# Control.net
KiCad netlist of a schematic drawn in Altium Designer
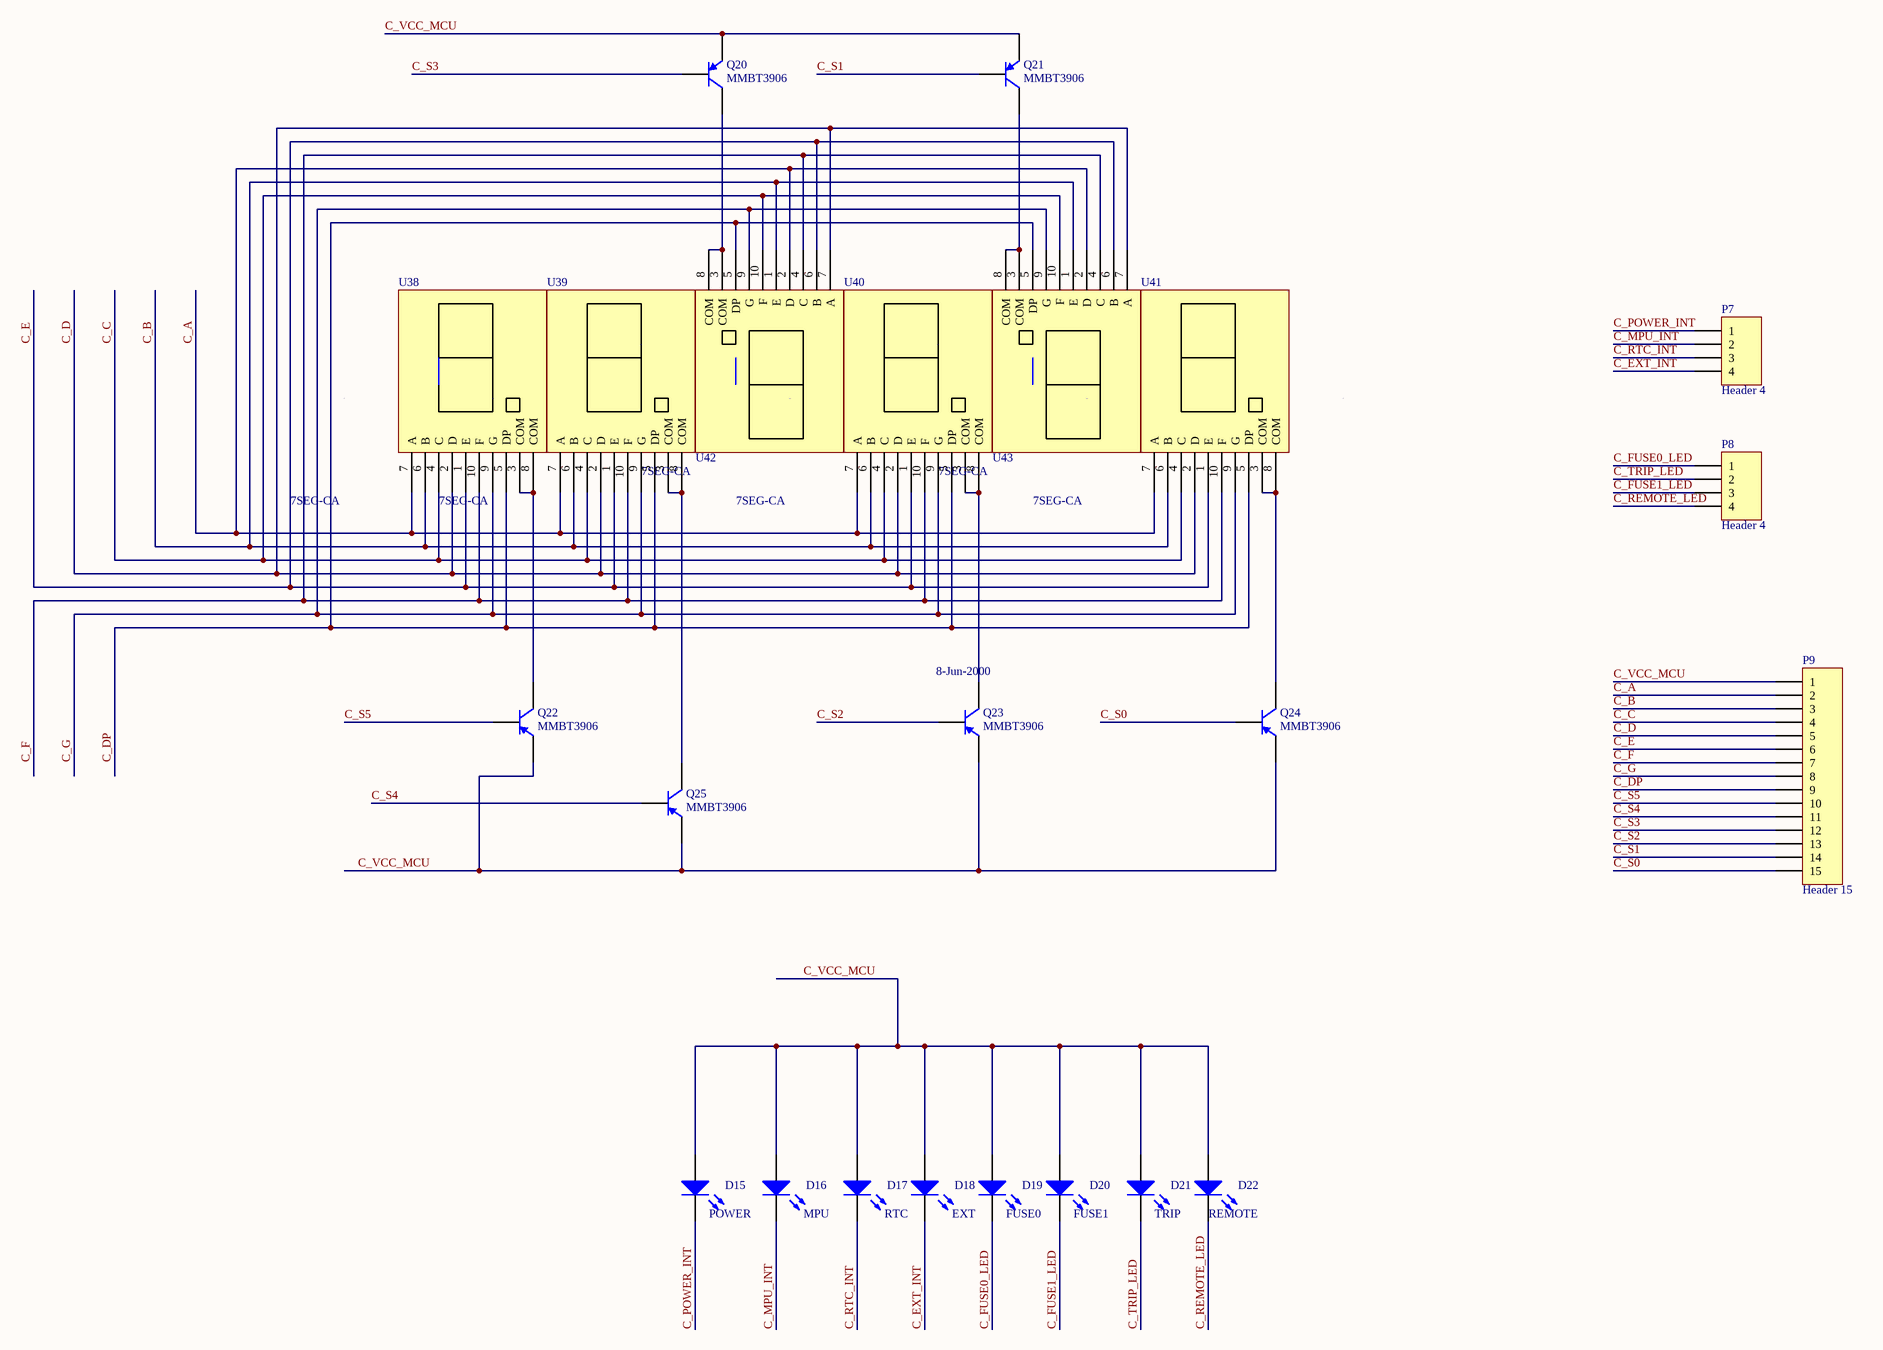
[diagram p0: Control.SchDoc]

(export (version "E")
  (design (tool "Eeschema 10.0.6"))
  (components
    (comp (ref "D15")
      (value "LED")
      (footprint "clock:0603D")
      (description "Typical RED, GREEN, YELLOW, AMBER GaAs LED")
      (fields (field (name "INFOR") "POWER") (field (name "PUBLISHER") "Altium Limited"))
      (libsource (lib "Miscellaneous Devices") (part "LED2"))
    )
    (comp (ref "D16")
      (value "LED")
      (footprint "clock:0603D")
      (description "Typical RED, GREEN, YELLOW, AMBER GaAs LED")
      (fields (field (name "INFO") "MPU") (field (name "PUBLISHER") "Altium Limited"))
      (libsource (lib "Miscellaneous Devices") (part "LED2"))
    )
    (comp (ref "D17")
      (value "LED")
      (footprint "clock:0603D")
      (description "Typical RED, GREEN, YELLOW, AMBER GaAs LED")
      (fields (field (name "INFO") "RTC") (field (name "PUBLISHER") "Altium Limited"))
      (libsource (lib "Miscellaneous Devices") (part "LED2"))
    )
    (comp (ref "D18")
      (value "LED")
      (footprint "clock:0603D")
      (description "Typical RED, GREEN, YELLOW, AMBER GaAs LED")
      (fields (field (name "INFO") "EXT") (field (name "PUBLISHER") "Altium Limited"))
      (libsource (lib "Miscellaneous Devices") (part "LED2"))
    )
    (comp (ref "D19")
      (value "LED")
      (footprint "clock:0603D")
      (description "Typical RED, GREEN, YELLOW, AMBER GaAs LED")
      (fields (field (name "INFO") "FUSE0") (field (name "PUBLISHER") "Altium Limited"))
      (libsource (lib "Miscellaneous Devices") (part "LED2"))
    )
    (comp (ref "D20")
      (value "LED")
      (footprint "clock:0603D")
      (description "Typical RED, GREEN, YELLOW, AMBER GaAs LED")
      (fields (field (name "INFO") "FUSE1") (field (name "PUBLISHER") "Altium Limited"))
      (libsource (lib "Miscellaneous Devices") (part "LED2"))
    )
    (comp (ref "D21")
      (value "LED")
      (footprint "clock:0603D")
      (description "Typical RED, GREEN, YELLOW, AMBER GaAs LED")
      (fields (field (name "INFO") "TRIP") (field (name "PUBLISHER") "Altium Limited"))
      (libsource (lib "Miscellaneous Devices") (part "LED2"))
    )
    (comp (ref "D22")
      (value "LED")
      (footprint "clock:0603D")
      (description "Typical RED, GREEN, YELLOW, AMBER GaAs LED")
      (fields (field (name "INFO") "REMOTE") (field (name "PUBLISHER") "Altium Limited"))
      (libsource (lib "Miscellaneous Devices") (part "LED2"))
    )
    (comp (ref "P7")
      (value "Header 4")
      (footprint "HDR1X4")
      (description "Header, 4-Pin")
      (fields (field (name "PUBLISHER") "Altium Limited"))
      (libsource (lib "Miscellaneous Connectors") (part "Header 4"))
    )
    (comp (ref "P8")
      (value "Header 4")
      (footprint "HDR1X4")
      (description "Header, 4-Pin")
      (fields (field (name "PUBLISHER") "Altium Limited"))
      (libsource (lib "Miscellaneous Connectors") (part "Header 4"))
    )
    (comp (ref "P9")
      (value "Header 15")
      (footprint "clock:HDR1X15")
      (description "Header, 15-Pin")
      (fields (field (name "PUBLISHER") "Altium Limited"))
      (libsource (lib "Miscellaneous Connectors") (part "Header 15"))
    )
    (comp (ref "Q20")
      (value "MMBT3906")
      (footprint "clock:SOT23-3-PNP")
      (description "PNP Bipolar Transistor")
      (fields (field (name "PUBLISHER") "Altium Limited"))
      (libsource (lib "Miscellaneous Devices") (part "PNP"))
    )
    (comp (ref "Q21")
      (value "MMBT3906")
      (footprint "clock:SOT23-3-PNP")
      (description "PNP Bipolar Transistor")
      (fields (field (name "PUBLISHER") "Altium Limited"))
      (libsource (lib "Miscellaneous Devices") (part "PNP"))
    )
    (comp (ref "Q22")
      (value "MMBT3906")
      (footprint "clock:SOT23-3-PNP")
      (description "PNP Bipolar Transistor")
      (fields (field (name "PUBLISHER") "Altium Limited"))
      (libsource (lib "Miscellaneous Devices") (part "PNP"))
    )
    (comp (ref "Q23")
      (value "MMBT3906")
      (footprint "clock:SOT23-3-PNP")
      (description "PNP Bipolar Transistor")
      (fields (field (name "PUBLISHED") "8-Jun-2000") (field (name "PUBLISHER") "Altium Limited"))
      (libsource (lib "Miscellaneous Devices") (part "PNP"))
    )
    (comp (ref "Q24")
      (value "MMBT3906")
      (footprint "clock:SOT23-3-PNP")
      (description "PNP Bipolar Transistor")
      (fields (field (name "PUBLISHER") "Altium Limited"))
      (libsource (lib "Miscellaneous Devices") (part "PNP"))
    )
    (comp (ref "Q25")
      (value "MMBT3906")
      (footprint "clock:SOT23-3-PNP")
      (description "PNP Bipolar Transistor")
      (fields (field (name "PUBLISHER") "Altium Limited"))
      (libsource (lib "Miscellaneous Devices") (part "PNP"))
    )
    (comp (ref "U38")
      (value "7SEG-CA")
      (footprint "clock:8SEC-CA-28")
      (libsource (lib "") (part "7SEG-CA_1"))
    )
    (comp (ref "U39")
      (value "7SEG-CA")
      (footprint "clock:8SEC-CA-28")
      (libsource (lib "") (part "7SEG-CA_1"))
    )
    (comp (ref "U40")
      (value "7SEG-CA")
      (footprint "clock:8SEC-CA-28")
      (libsource (lib "") (part "7SEG-CA_1"))
    )
    (comp (ref "U41")
      (value "7SEG-CA")
      (footprint "clock:8SEC-CA-28")
      (libsource (lib "") (part "7SEG-CA_1"))
    )
    (comp (ref "U42")
      (value "7SEG-CA")
      (footprint "clock:8SEC-CA-28")
      (libsource (lib "clock") (part "7SEG-CA"))
    )
    (comp (ref "U43")
      (value "7SEG-CA")
      (footprint "clock:8SEC-CA-28")
      (libsource (lib "clock") (part "7SEG-CA"))
    )
  )
  (nets
    (net (code "1") (name "/C_A") (class "Default")
      (node (ref "P9") (pin "2") (pinfunction "2_2") (pintype "passive"))
      (node (ref "U38") (pin "7") (pinfunction "A_7") (pintype "passive"))
      (node (ref "U39") (pin "7") (pinfunction "A_7") (pintype "passive"))
      (node (ref "U40") (pin "7") (pinfunction "A_7") (pintype "passive"))
      (node (ref "U41") (pin "7") (pinfunction "A_7") (pintype "passive"))
      (node (ref "U42") (pin "2") (pinfunction "D_2") (pintype "passive"))
      (node (ref "U43") (pin "2") (pinfunction "D_2") (pintype "passive"))
    )
    (net (code "2") (name "/C_B") (class "Default")
      (node (ref "P9") (pin "3") (pinfunction "3_3") (pintype "passive"))
      (node (ref "U38") (pin "6") (pinfunction "B_6") (pintype "passive"))
      (node (ref "U39") (pin "6") (pinfunction "B_6") (pintype "passive"))
      (node (ref "U40") (pin "6") (pinfunction "B_6") (pintype "passive"))
      (node (ref "U41") (pin "6") (pinfunction "B_6") (pintype "passive"))
      (node (ref "U42") (pin "1") (pinfunction "E_1") (pintype "passive"))
      (node (ref "U43") (pin "1") (pinfunction "E_1") (pintype "passive"))
    )
    (net (code "3") (name "/C_C") (class "Default")
      (node (ref "P9") (pin "4") (pinfunction "4_4") (pintype "passive"))
      (node (ref "U38") (pin "4") (pinfunction "C_4") (pintype "passive"))
      (node (ref "U39") (pin "4") (pinfunction "C_4") (pintype "passive"))
      (node (ref "U40") (pin "4") (pinfunction "C_4") (pintype "passive"))
      (node (ref "U41") (pin "4") (pinfunction "C_4") (pintype "passive"))
      (node (ref "U42") (pin "10") (pinfunction "F_10") (pintype "passive"))
      (node (ref "U43") (pin "10") (pinfunction "F_10") (pintype "passive"))
    )
    (net (code "4") (name "/C_D") (class "Default")
      (node (ref "P9") (pin "5") (pinfunction "5_5") (pintype "passive"))
      (node (ref "U38") (pin "2") (pinfunction "D_2") (pintype "passive"))
      (node (ref "U39") (pin "2") (pinfunction "D_2") (pintype "passive"))
      (node (ref "U40") (pin "2") (pinfunction "D_2") (pintype "passive"))
      (node (ref "U41") (pin "2") (pinfunction "D_2") (pintype "passive"))
      (node (ref "U42") (pin "7") (pinfunction "A_7") (pintype "passive"))
      (node (ref "U43") (pin "7") (pinfunction "A_7") (pintype "passive"))
    )
    (net (code "5") (name "/C_DP") (class "Default")
      (node (ref "P9") (pin "9") (pinfunction "9_9") (pintype "passive"))
      (node (ref "U38") (pin "5") (pinfunction "DP_5") (pintype "passive"))
      (node (ref "U39") (pin "5") (pinfunction "DP_5") (pintype "passive"))
      (node (ref "U40") (pin "5") (pinfunction "DP_5") (pintype "passive"))
      (node (ref "U41") (pin "5") (pinfunction "DP_5") (pintype "passive"))
      (node (ref "U42") (pin "5") (pinfunction "DP_5") (pintype "passive"))
      (node (ref "U43") (pin "5") (pinfunction "DP_5") (pintype "passive"))
    )
    (net (code "6") (name "/C_E") (class "Default")
      (node (ref "P9") (pin "6") (pinfunction "6_6") (pintype "passive"))
      (node (ref "U38") (pin "1") (pinfunction "E_1") (pintype "passive"))
      (node (ref "U39") (pin "1") (pinfunction "E_1") (pintype "passive"))
      (node (ref "U40") (pin "1") (pinfunction "E_1") (pintype "passive"))
      (node (ref "U41") (pin "1") (pinfunction "E_1") (pintype "passive"))
      (node (ref "U42") (pin "6") (pinfunction "B_6") (pintype "passive"))
      (node (ref "U43") (pin "6") (pinfunction "B_6") (pintype "passive"))
    )
    (net (code "7") (name "/C_EXT_INT") (class "Default")
      (node (ref "D18") (pin "2") (pinfunction "K_2") (pintype "passive"))
      (node (ref "P7") (pin "4") (pinfunction "4_4") (pintype "passive"))
    )
    (net (code "8") (name "/C_F") (class "Default")
      (node (ref "P9") (pin "7") (pinfunction "7_7") (pintype "passive"))
      (node (ref "U38") (pin "10") (pinfunction "F_10") (pintype "passive"))
      (node (ref "U39") (pin "10") (pinfunction "F_10") (pintype "passive"))
      (node (ref "U40") (pin "10") (pinfunction "F_10") (pintype "passive"))
      (node (ref "U41") (pin "10") (pinfunction "F_10") (pintype "passive"))
      (node (ref "U42") (pin "4") (pinfunction "C_4") (pintype "passive"))
      (node (ref "U43") (pin "4") (pinfunction "C_4") (pintype "passive"))
    )
    (net (code "9") (name "/C_FUSE0_LED") (class "Default")
      (node (ref "D19") (pin "2") (pinfunction "K_2") (pintype "passive"))
      (node (ref "P8") (pin "1") (pinfunction "1_1") (pintype "passive"))
    )
    (net (code "10") (name "/C_FUSE1_LED") (class "Default")
      (node (ref "D20") (pin "2") (pinfunction "K_2") (pintype "passive"))
      (node (ref "P8") (pin "3") (pinfunction "3_3") (pintype "passive"))
    )
    (net (code "11") (name "/C_G") (class "Default")
      (node (ref "P9") (pin "8") (pinfunction "8_8") (pintype "passive"))
      (node (ref "U38") (pin "9") (pinfunction "G_9") (pintype "passive"))
      (node (ref "U39") (pin "9") (pinfunction "G_9") (pintype "passive"))
      (node (ref "U40") (pin "9") (pinfunction "G_9") (pintype "passive"))
      (node (ref "U41") (pin "9") (pinfunction "G_9") (pintype "passive"))
      (node (ref "U42") (pin "9") (pinfunction "G_9") (pintype "passive"))
      (node (ref "U43") (pin "9") (pinfunction "G_9") (pintype "passive"))
    )
    (net (code "12") (name "/C_MPU_INT") (class "Default")
      (node (ref "D16") (pin "2") (pinfunction "K_2") (pintype "passive"))
      (node (ref "P7") (pin "2") (pinfunction "2_2") (pintype "passive"))
    )
    (net (code "13") (name "/C_POWER_INT") (class "Default")
      (node (ref "D15") (pin "2") (pinfunction "K_2") (pintype "passive"))
      (node (ref "P7") (pin "1") (pinfunction "1_1") (pintype "passive"))
    )
    (net (code "14") (name "/C_REMOTE_LED") (class "Default")
      (node (ref "D22") (pin "2") (pinfunction "K_2") (pintype "passive"))
      (node (ref "P8") (pin "4") (pinfunction "4_4") (pintype "passive"))
    )
    (net (code "15") (name "/C_RTC_INT") (class "Default")
      (node (ref "D17") (pin "2") (pinfunction "K_2") (pintype "passive"))
      (node (ref "P7") (pin "3") (pinfunction "3_3") (pintype "passive"))
    )
    (net (code "16") (name "/C_S0") (class "Default")
      (node (ref "P9") (pin "15") (pinfunction "15_15") (pintype "passive"))
      (node (ref "Q24") (pin "2") (pinfunction "B_2") (pintype "passive"))
    )
    (net (code "17") (name "/C_S1") (class "Default")
      (node (ref "P9") (pin "14") (pinfunction "14_14") (pintype "passive"))
      (node (ref "Q21") (pin "2") (pinfunction "B_2") (pintype "passive"))
    )
    (net (code "18") (name "/C_S2") (class "Default")
      (node (ref "P9") (pin "13") (pinfunction "13_13") (pintype "passive"))
      (node (ref "Q23") (pin "2") (pinfunction "B_2") (pintype "passive"))
    )
    (net (code "19") (name "/C_S3") (class "Default")
      (node (ref "P9") (pin "12") (pinfunction "12_12") (pintype "passive"))
      (node (ref "Q20") (pin "2") (pinfunction "B_2") (pintype "passive"))
    )
    (net (code "20") (name "/C_S4") (class "Default")
      (node (ref "P9") (pin "11") (pinfunction "11_11") (pintype "passive"))
      (node (ref "Q25") (pin "2") (pinfunction "B_2") (pintype "passive"))
    )
    (net (code "21") (name "/C_S5") (class "Default")
      (node (ref "P9") (pin "10") (pinfunction "10_10") (pintype "passive"))
      (node (ref "Q22") (pin "2") (pinfunction "B_2") (pintype "passive"))
    )
    (net (code "22") (name "/C_TRIP_LED") (class "Default")
      (node (ref "D21") (pin "2") (pinfunction "K_2") (pintype "passive"))
      (node (ref "P8") (pin "2") (pinfunction "2_2") (pintype "passive"))
    )
    (net (code "23") (name "/C_VCC_MCU") (class "Default")
      (node (ref "D15") (pin "1") (pinfunction "A_1") (pintype "passive"))
      (node (ref "D16") (pin "1") (pinfunction "A_1") (pintype "passive"))
      (node (ref "D17") (pin "1") (pinfunction "A_1") (pintype "passive"))
      (node (ref "D18") (pin "1") (pinfunction "A_1") (pintype "passive"))
      (node (ref "D19") (pin "1") (pinfunction "A_1") (pintype "passive"))
      (node (ref "D20") (pin "1") (pinfunction "A_1") (pintype "passive"))
      (node (ref "D21") (pin "1") (pinfunction "A_1") (pintype "passive"))
      (node (ref "D22") (pin "1") (pinfunction "A_1") (pintype "passive"))
      (node (ref "P9") (pin "1") (pinfunction "1_1") (pintype "passive"))
      (node (ref "Q20") (pin "3") (pinfunction "E_3") (pintype "passive"))
      (node (ref "Q21") (pin "3") (pinfunction "E_3") (pintype "passive"))
      (node (ref "Q22") (pin "3") (pinfunction "E_3") (pintype "passive"))
      (node (ref "Q23") (pin "3") (pinfunction "E_3") (pintype "passive"))
      (node (ref "Q24") (pin "3") (pinfunction "E_3") (pintype "passive"))
      (node (ref "Q25") (pin "3") (pinfunction "E_3") (pintype "passive"))
    )
    (net (code "24") (name "Net-(Q20-C)") (class "Default")
      (node (ref "Q20") (pin "1") (pinfunction "C_1") (pintype "passive"))
      (node (ref "U42") (pin "3") (pinfunction "COM_3") (pintype "passive"))
      (node (ref "U42") (pin "8") (pinfunction "COM_8") (pintype "passive"))
    )
    (net (code "25") (name "Net-(Q21-C)") (class "Default")
      (node (ref "Q21") (pin "1") (pinfunction "C_1") (pintype "passive"))
      (node (ref "U43") (pin "3") (pinfunction "COM_3") (pintype "passive"))
      (node (ref "U43") (pin "8") (pinfunction "COM_8") (pintype "passive"))
    )
    (net (code "26") (name "Net-(Q22-C)") (class "Default")
      (node (ref "Q22") (pin "1") (pinfunction "C_1") (pintype "passive"))
      (node (ref "U38") (pin "3") (pinfunction "COM_3") (pintype "passive"))
      (node (ref "U38") (pin "8") (pinfunction "COM_8") (pintype "passive"))
    )
    (net (code "27") (name "Net-(Q23-C)") (class "Default")
      (node (ref "Q23") (pin "1") (pinfunction "C_1") (pintype "passive"))
      (node (ref "U40") (pin "3") (pinfunction "COM_3") (pintype "passive"))
      (node (ref "U40") (pin "8") (pinfunction "COM_8") (pintype "passive"))
    )
    (net (code "28") (name "Net-(Q24-C)") (class "Default")
      (node (ref "Q24") (pin "1") (pinfunction "C_1") (pintype "passive"))
      (node (ref "U41") (pin "3") (pinfunction "COM_3") (pintype "passive"))
      (node (ref "U41") (pin "8") (pinfunction "COM_8") (pintype "passive"))
    )
    (net (code "29") (name "Net-(Q25-C)") (class "Default")
      (node (ref "Q25") (pin "1") (pinfunction "C_1") (pintype "passive"))
      (node (ref "U39") (pin "3") (pinfunction "COM_3") (pintype "passive"))
      (node (ref "U39") (pin "8") (pinfunction "COM_8") (pintype "passive"))
    )
  )
)
